# esp8266_ir_blaster.net
KiCad netlist of a schematic drawn in EAGLE
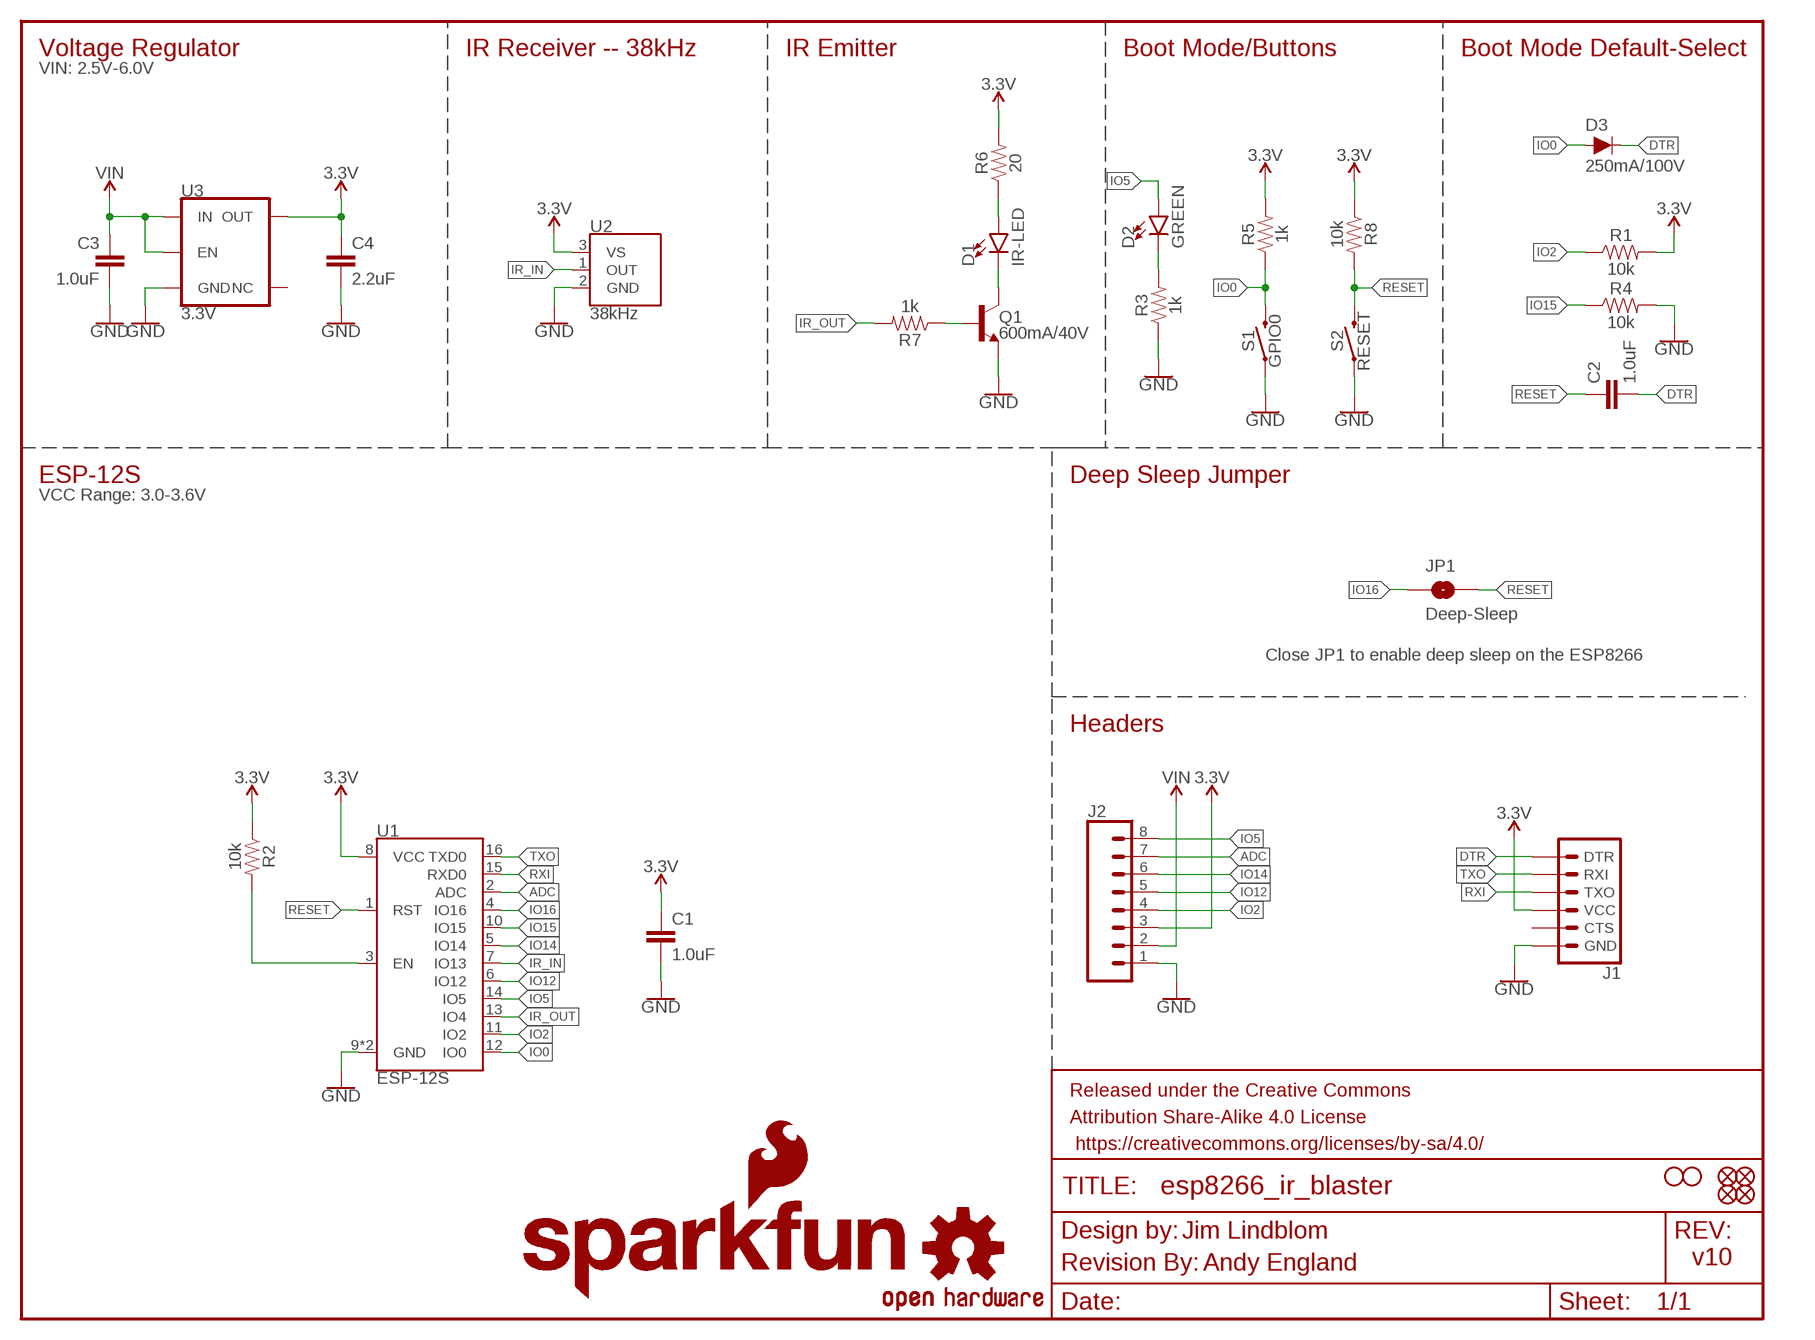
[diagram p0: schematic, sheet 1]

(export (version "E")
  (design (tool "Eeschema 10.0.6"))
  (components
    (comp (ref "C1")
      (value "1.0uF")
      (footprint "eagle-import:0603")
      (libsource (lib "eagle-import") (part "1.0UF-0603-16V-10%"))
    )
    (comp (ref "C2")
      (value "1.0uF")
      (footprint "eagle-import:0603")
      (libsource (lib "eagle-import") (part "1.0UF-0603-16V-10%"))
    )
    (comp (ref "C3")
      (value "1.0uF")
      (footprint "eagle-import:0603")
      (libsource (lib "eagle-import") (part "1.0UF-0603-16V-10%"))
    )
    (comp (ref "C4")
      (value "2.2uF")
      (footprint "eagle-import:0603")
      (libsource (lib "eagle-import") (part "2.2UF-0603-10V-20%"))
    )
    (comp (ref "D1")
      (value "IR-LED")
      (footprint "eagle-import:LTE-302")
      (libsource (lib "eagle-import") (part "LED-IRSIDE_EMITTER"))
    )
    (comp (ref "D2")
      (value "GREEN")
      (footprint "eagle-import:LED-0603")
      (libsource (lib "eagle-import") (part "LED-GREEN0603"))
    )
    (comp (ref "D3")
      (value "250mA/100V")
      (footprint "eagle-import:SOD-323")
      (libsource (lib "eagle-import") (part "DIODE-BAS16J"))
    )
    (comp (ref "FD1")
      (value "FIDUCIALUFIDUCIAL")
      (footprint "eagle-import:FIDUCIAL-MICRO")
      (libsource (lib "eagle-import") (part "FIDUCIALUFIDUCIAL"))
    )
    (comp (ref "FD2")
      (value "FIDUCIALUFIDUCIAL")
      (footprint "eagle-import:FIDUCIAL-MICRO")
      (libsource (lib "eagle-import") (part "FIDUCIALUFIDUCIAL"))
    )
    (comp (ref "FD3")
      (value "FIDUCIALUFIDUCIAL")
      (footprint "eagle-import:FIDUCIAL-MICRO")
      (libsource (lib "eagle-import") (part "FIDUCIALUFIDUCIAL"))
    )
    (comp (ref "FD4")
      (value "FIDUCIALUFIDUCIAL")
      (footprint "eagle-import:FIDUCIAL-MICRO")
      (libsource (lib "eagle-import") (part "FIDUCIALUFIDUCIAL"))
    )
    (comp (ref "FRAME1")
      (value "FRAME-LETTER")
      (footprint "eagle-import:CREATIVE_COMMONS")
      (libsource (lib "eagle-import") (part "FRAME-LETTER"))
    )
    (comp (ref "H1")
      (value "STAND-OFF")
      (footprint "eagle-import:STAND-OFF")
      (libsource (lib "eagle-import") (part "STAND-OFF"))
    )
    (comp (ref "H2")
      (value "STAND-OFF")
      (footprint "eagle-import:STAND-OFF")
      (libsource (lib "eagle-import") (part "STAND-OFF"))
    )
    (comp (ref "J1")
      (value "6_PIN_SERIAL_TARGETNO_SILK")
      (footprint "eagle-import:1X06_NO_SILK")
      (libsource (lib "eagle-import") (part "6_PIN_SERIAL_TARGETNO_SILK"))
    )
    (comp (ref "J2")
      (value "CONN_08NO_SILK_FEMALE_PTH")
      (footprint "eagle-import:1X08_NO_SILK")
      (libsource (lib "eagle-import") (part "CONN_08NO_SILK_FEMALE_PTH"))
    )
    (comp (ref "JP1")
      (value "Deep-Sleep")
      (footprint "eagle-import:SMT-JUMPER_2_NO_NO-SILK")
      (libsource (lib "eagle-import") (part "JUMPER-SMT_2_NO_NO-SILK"))
    )
    (comp (ref "LOGO1")
      (value "OSHW-LOGOS")
      (footprint "eagle-import:OSHW-LOGO-S")
      (libsource (lib "eagle-import") (part "OSHW-LOGOS"))
    )
    (comp (ref "LOGO2")
      (value "SFE_LOGO_NAME_FLAME.1_INCH")
      (footprint "eagle-import:SFE_LOGO_NAME_FLAME_.1")
      (libsource (lib "eagle-import") (part "SFE_LOGO_NAME_FLAME.1_INCH"))
    )
    (comp (ref "LOGO3")
      (value "REVISION")
      (footprint "eagle-import:REVISION")
      (libsource (lib "eagle-import") (part "REVISION"))
    )
    (comp (ref "Q1")
      (value "600mA/40V")
      (footprint "eagle-import:SOT23-3")
      (libsource (lib "eagle-import") (part "TRANS_NPN-MMBT2222AL"))
    )
    (comp (ref "R1")
      (value "10k")
      (footprint "eagle-import:0603")
      (libsource (lib "eagle-import") (part "10KOHM-0603-1/10W-1%"))
    )
    (comp (ref "R2")
      (value "10k")
      (footprint "eagle-import:0603")
      (libsource (lib "eagle-import") (part "10KOHM-0603-1/10W-1%"))
    )
    (comp (ref "R3")
      (value "1k")
      (footprint "eagle-import:0603")
      (libsource (lib "eagle-import") (part "1KOHM-0603-1/10W-1%"))
    )
    (comp (ref "R4")
      (value "10k")
      (footprint "eagle-import:0603")
      (libsource (lib "eagle-import") (part "10KOHM-0603-1/10W-1%"))
    )
    (comp (ref "R5")
      (value "1k")
      (footprint "eagle-import:0603")
      (libsource (lib "eagle-import") (part "1KOHM-0603-1/10W-1%"))
    )
    (comp (ref "R6")
      (value "20")
      (footprint "eagle-import:0603")
      (libsource (lib "eagle-import") (part "20OHM-0603-1/10W-1%"))
    )
    (comp (ref "R7")
      (value "1k")
      (footprint "eagle-import:0603")
      (libsource (lib "eagle-import") (part "1KOHM-0603-1/10W-1%"))
    )
    (comp (ref "R8")
      (value "10k")
      (footprint "eagle-import:0603")
      (libsource (lib "eagle-import") (part "10KOHM-0603-1/10W-1%"))
    )
    (comp (ref "S1")
      (value "GPIO0")
      (footprint "eagle-import:TACTILE_SWITCH_SMD_4.6X2.8MM")
      (libsource (lib "eagle-import") (part "MOMENTARY-SWITCH-SPST-SMD-4.6X2.8MM"))
    )
    (comp (ref "S2")
      (value "RESET")
      (footprint "eagle-import:TACTILE_SWITCH_SMD_4.6X2.8MM")
      (libsource (lib "eagle-import") (part "MOMENTARY-SWITCH-SPST-SMD-4.6X2.8MM"))
    )
    (comp (ref "U1")
      (value "ESP-12S")
      (footprint "eagle-import:ESP-12S")
      (libsource (lib "eagle-import") (part "ESP-12S"))
    )
    (comp (ref "U2")
      (value "38kHz")
      (footprint "eagle-import:TSOP382")
      (libsource (lib "eagle-import") (part "TSOP38238"))
    )
    (comp (ref "U3")
      (value "3.3V")
      (footprint "eagle-import:SOT23-5")
      (libsource (lib "eagle-import") (part "V_REG_AP2112K-3.3V"))
    )
  )
  (nets
    (net (code "1") (name "3.3V") (class "Default")
      (node (ref "C1") (pin "1") (pinfunction "1_1") (pintype "passive"))
      (node (ref "C4") (pin "1") (pinfunction "1_1") (pintype "passive"))
      (node (ref "J1") (pin "4") (pinfunction "VCC_4") (pintype "passive"))
      (node (ref "J2") (pin "3") (pinfunction "3_3") (pintype "passive"))
      (node (ref "R1") (pin "2") (pinfunction "2_2") (pintype "passive"))
      (node (ref "R2") (pin "1") (pinfunction "1_1") (pintype "passive"))
      (node (ref "R5") (pin "2") (pinfunction "2_2") (pintype "passive"))
      (node (ref "R6") (pin "2") (pinfunction "2_2") (pintype "passive"))
      (node (ref "R8") (pin "1") (pinfunction "1_1") (pintype "passive"))
      (node (ref "U1") (pin "8") (pinfunction "VCC_8") (pintype "bidirectional"))
      (node (ref "U2") (pin "3") (pinfunction "VS_3") (pintype "bidirectional"))
      (node (ref "U3") (pin "5") (pinfunction "OUT_5") (pintype "passive"))
    )
    (net (code "2") (name "ADC") (class "Default")
      (node (ref "J2") (pin "7") (pinfunction "7_7") (pintype "passive"))
      (node (ref "U1") (pin "2") (pinfunction "ADC_2") (pintype "bidirectional"))
    )
    (net (code "3") (name "DTR") (class "Default")
      (node (ref "C2") (pin "2") (pinfunction "2_2") (pintype "passive"))
      (node (ref "D3") (pin "C") (pinfunction "C_C") (pintype "passive"))
      (node (ref "J1") (pin "1") (pinfunction "DTR_1") (pintype "passive"))
    )
    (net (code "4") (name "GND") (class "Default")
      (node (ref "C1") (pin "2") (pinfunction "2_2") (pintype "passive"))
      (node (ref "C3") (pin "2") (pinfunction "2_2") (pintype "passive"))
      (node (ref "C4") (pin "2") (pinfunction "2_2") (pintype "passive"))
      (node (ref "J1") (pin "6") (pinfunction "GND_6") (pintype "passive"))
      (node (ref "J2") (pin "1") (pinfunction "1_1") (pintype "passive"))
      (node (ref "Q1") (pin "2") (pinfunction "E_2") (pintype "passive"))
      (node (ref "R3") (pin "1") (pinfunction "1_1") (pintype "passive"))
      (node (ref "R4") (pin "2") (pinfunction "2_2") (pintype "passive"))
      (node (ref "S1") (pin "1") (pinfunction "1_1") (pintype "passive"))
      (node (ref "S1") (pin "2") (pinfunction "1_2") (pintype "passive"))
      (node (ref "S2") (pin "1") (pinfunction "1_1") (pintype "passive"))
      (node (ref "S2") (pin "2") (pinfunction "1_2") (pintype "passive"))
      (node (ref "U1") (pin "9") (pinfunction "GND_9") (pintype "bidirectional"))
      (node (ref "U1") (pin "P$1") (pinfunction "GND_P$1") (pintype "bidirectional"))
      (node (ref "U2") (pin "2") (pinfunction "GND_2") (pintype "bidirectional"))
      (node (ref "U3") (pin "2") (pinfunction "GND_2") (pintype "input"))
    )
    (net (code "5") (name "IO0") (class "Default")
      (node (ref "D3") (pin "A") (pinfunction "A_A") (pintype "passive"))
      (node (ref "R5") (pin "1") (pinfunction "1_1") (pintype "passive"))
      (node (ref "S1") (pin "3") (pinfunction "2_3") (pintype "passive"))
      (node (ref "S1") (pin "4") (pinfunction "2_4") (pintype "passive"))
      (node (ref "U1") (pin "12") (pinfunction "IO0_12") (pintype "bidirectional"))
    )
    (net (code "6") (name "IO2") (class "Default")
      (node (ref "J2") (pin "4") (pinfunction "4_4") (pintype "passive"))
      (node (ref "R1") (pin "1") (pinfunction "1_1") (pintype "passive"))
      (node (ref "U1") (pin "11") (pinfunction "IO2_11") (pintype "bidirectional"))
    )
    (net (code "7") (name "IO5") (class "Default")
      (node (ref "D2") (pin "A") (pinfunction "A_A") (pintype "passive"))
      (node (ref "J2") (pin "8") (pinfunction "8_8") (pintype "passive"))
      (node (ref "U1") (pin "14") (pinfunction "IO5_14") (pintype "bidirectional"))
    )
    (net (code "8") (name "IO12") (class "Default")
      (node (ref "J2") (pin "5") (pinfunction "5_5") (pintype "passive"))
      (node (ref "U1") (pin "6") (pinfunction "IO12_6") (pintype "bidirectional"))
    )
    (net (code "9") (name "IO14") (class "Default")
      (node (ref "J2") (pin "6") (pinfunction "6_6") (pintype "passive"))
      (node (ref "U1") (pin "5") (pinfunction "IO14_5") (pintype "bidirectional"))
    )
    (net (code "10") (name "IO15") (class "Default")
      (node (ref "R4") (pin "1") (pinfunction "1_1") (pintype "passive"))
      (node (ref "U1") (pin "10") (pinfunction "IO15_10") (pintype "bidirectional"))
    )
    (net (code "11") (name "IO16") (class "Default")
      (node (ref "JP1") (pin "1") (pinfunction "1_1") (pintype "passive"))
      (node (ref "U1") (pin "4") (pinfunction "IO16_4") (pintype "bidirectional"))
    )
    (net (code "12") (name "IR_IN") (class "Default")
      (node (ref "U1") (pin "7") (pinfunction "IO13_7") (pintype "bidirectional"))
      (node (ref "U2") (pin "1") (pinfunction "OUT_1") (pintype "bidirectional"))
    )
    (net (code "13") (name "IR_OUT") (class "Default")
      (node (ref "R7") (pin "2") (pinfunction "2_2") (pintype "passive"))
      (node (ref "U1") (pin "13") (pinfunction "IO4_13") (pintype "bidirectional"))
    )
    (net (code "14") (name "Net-(D1-PadA)") (class "Default")
      (node (ref "D1") (pin "A") (pinfunction "A_A") (pintype "passive"))
      (node (ref "R6") (pin "1") (pinfunction "1_1") (pintype "passive"))
    )
    (net (code "15") (name "Net-(D2-PadC)") (class "Default")
      (node (ref "D2") (pin "C") (pinfunction "C_C") (pintype "passive"))
      (node (ref "R3") (pin "2") (pinfunction "2_2") (pintype "passive"))
    )
    (net (code "16") (name "Net-(Q1-B)") (class "Default")
      (node (ref "Q1") (pin "1") (pinfunction "B_1") (pintype "passive"))
      (node (ref "R7") (pin "1") (pinfunction "1_1") (pintype "passive"))
    )
    (net (code "17") (name "Net-(Q1-C)") (class "Default")
      (node (ref "D1") (pin "C") (pinfunction "C_C") (pintype "passive"))
      (node (ref "Q1") (pin "3") (pinfunction "C_3") (pintype "passive"))
    )
    (net (code "18") (name "Net-(U1-EN)") (class "Default")
      (node (ref "R2") (pin "2") (pinfunction "2_2") (pintype "passive"))
      (node (ref "U1") (pin "3") (pinfunction "EN_3") (pintype "bidirectional"))
    )
    (net (code "19") (name "RESET") (class "Default")
      (node (ref "C2") (pin "1") (pinfunction "1_1") (pintype "passive"))
      (node (ref "JP1") (pin "2") (pinfunction "2_2") (pintype "passive"))
      (node (ref "R8") (pin "2") (pinfunction "2_2") (pintype "passive"))
      (node (ref "S2") (pin "3") (pinfunction "2_3") (pintype "passive"))
      (node (ref "S2") (pin "4") (pinfunction "2_4") (pintype "passive"))
      (node (ref "U1") (pin "1") (pinfunction "RST_1") (pintype "bidirectional"))
    )
    (net (code "20") (name "RXI") (class "Default")
      (node (ref "J1") (pin "3") (pinfunction "TXO_3") (pintype "passive"))
      (node (ref "U1") (pin "15") (pinfunction "RXD0_15") (pintype "bidirectional"))
    )
    (net (code "21") (name "TXO") (class "Default")
      (node (ref "J1") (pin "2") (pinfunction "RXI_2") (pintype "passive"))
      (node (ref "U1") (pin "16") (pinfunction "TXD0_16") (pintype "bidirectional"))
    )
    (net (code "22") (name "VIN") (class "Default")
      (node (ref "C3") (pin "1") (pinfunction "1_1") (pintype "passive"))
      (node (ref "J2") (pin "2") (pinfunction "2_2") (pintype "passive"))
      (node (ref "U3") (pin "1") (pinfunction "IN_1") (pintype "input"))
      (node (ref "U3") (pin "3") (pinfunction "EN_3") (pintype "input"))
    )
    (net (code "23") (name "unconnected-(J1-CTS-Pad5)") (class "Default")
      (node (ref "J1") (pin "5") (pinfunction "CTS_5") (pintype "passive"))
    )
    (net (code "24") (name "unconnected-(U3-NC-Pad4)") (class "Default")
      (node (ref "U3") (pin "4") (pinfunction "NC_4") (pintype "no_connect"))
    )
  )
)
